# MainBoard_MCUBreakout.net
KiCad netlist of a schematic drawn in Altium Designer
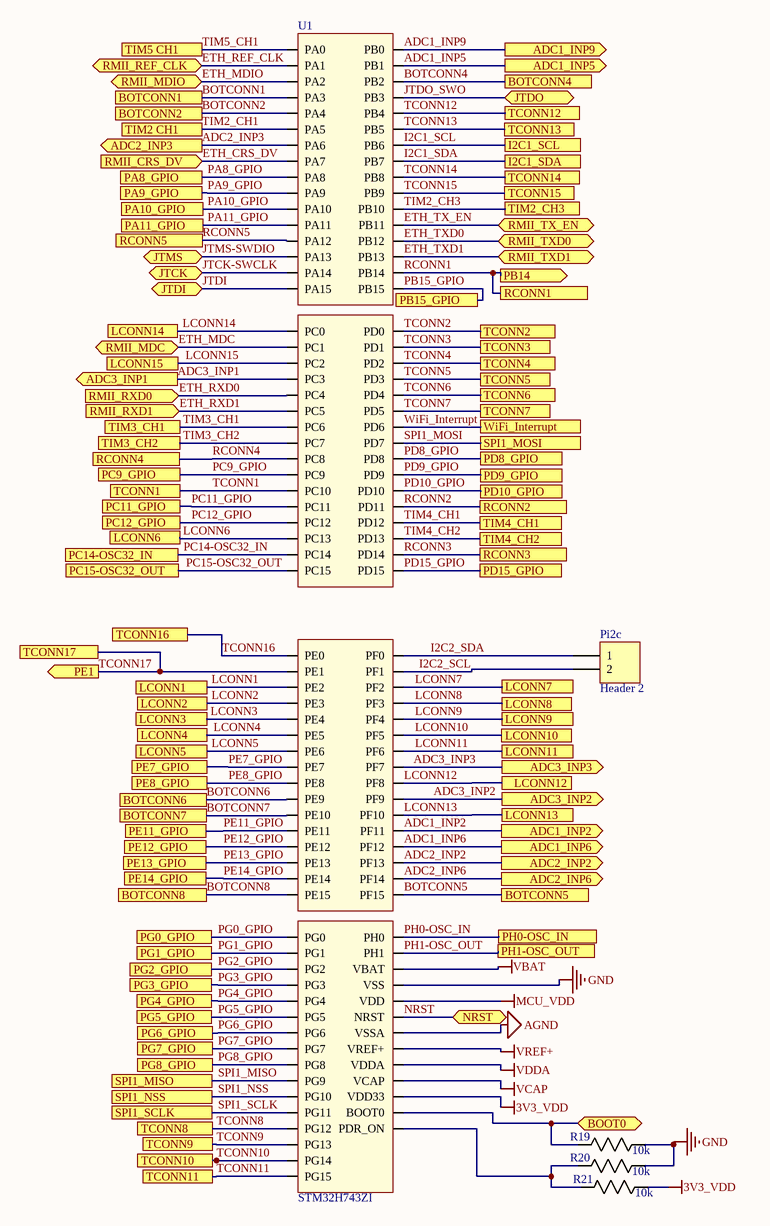
[diagram p0: MainBoard_MCUBreakout.SchDoc]

(export (version "E")
  (design (tool "Eeschema 10.0.6"))
  (components
    (comp (ref "Pi2c")
      (value "Header 2")
      (footprint "HDR1X2")
      (description "Header, 2-Pin")
      (fields (field (name "PUBLISHER") "Altium Limited"))
      (libsource (lib "Miscellaneous Connectors") (part "Header 2"))
    )
    (comp (ref "R19")
      (value "10k")
      (footprint "0805")
      (description "RES SMD 10K OHM 1% 1/8W 0805")
      (fields (field (name "MP") "RC0805FR-0710KL") (field (name "MF") "Yageo"))
      (libsource (lib "AltiumLibraries") (part "RES 10k 0805"))
    )
    (comp (ref "R20")
      (value "10k")
      (footprint "0805")
      (description "RES SMD 10K OHM 1% 1/8W 0805")
      (fields (field (name "MP") "RC0805FR-0710KL") (field (name "MF") "Yageo"))
      (libsource (lib "AltiumLibraries") (part "RES 10k 0805"))
    )
    (comp (ref "R21")
      (value "10k")
      (footprint "0805")
      (description "RES SMD 10K OHM 1% 1/8W 0805")
      (fields (field (name "MP") "RC0805FR-0710KL") (field (name "MF") "Yageo"))
      (libsource (lib "AltiumLibraries") (part "RES 10k 0805"))
    )
    (comp (ref "U1")
      (value "STM32H743ZI")
      (footprint "STM32H7")
      (fields (field (name "MF") "STMicroelectronics") (field (name "MP") "STM32H743ZIT6"))
      (libsource (lib "AltiumLibraries") (part "STM32H743ZI"))
    )
  )
  (nets
    (net (code "1") (name "/ADC1_INP2") (class "Default")
      (node (ref "U1") (pin "PF11") (pinfunction "PF11_PF11") (pintype "passive"))
    )
    (net (code "2") (name "/ADC1_INP5") (class "Default")
      (node (ref "U1") (pin "PB1") (pinfunction "PB1_PB1") (pintype "passive"))
    )
    (net (code "3") (name "/ADC1_INP6") (class "Default")
      (node (ref "U1") (pin "PF12") (pinfunction "PF12_PF12") (pintype "passive"))
    )
    (net (code "4") (name "/ADC1_INP9") (class "Default")
      (node (ref "U1") (pin "PB0") (pinfunction "PB0_PB0") (pintype "passive"))
    )
    (net (code "5") (name "/ADC2_INP2") (class "Default")
      (node (ref "U1") (pin "PF13") (pinfunction "PF13_PF13") (pintype "passive"))
    )
    (net (code "6") (name "/ADC2_INP3") (class "Default")
      (node (ref "U1") (pin "PA6") (pinfunction "PA6_PA6") (pintype "passive"))
    )
    (net (code "7") (name "/ADC2_INP6") (class "Default")
      (node (ref "U1") (pin "PF14") (pinfunction "PF14_PF14") (pintype "passive"))
    )
    (net (code "8") (name "/ADC3_INP1") (class "Default")
      (node (ref "U1") (pin "PC3") (pinfunction "PC3_PC3") (pintype "passive"))
    )
    (net (code "9") (name "/ADC3_INP2") (class "Default")
      (node (ref "U1") (pin "PF9") (pinfunction "PF9_PF9") (pintype "passive"))
    )
    (net (code "10") (name "/ADC3_INP3") (class "Default")
      (node (ref "U1") (pin "PF7") (pinfunction "PF7_PF7") (pintype "passive"))
    )
    (net (code "11") (name "/BOOT0") (class "Default")
      (node (ref "R19") (pin "2") (pinfunction "R2_2") (pintype "passive"))
      (node (ref "U1") (pin "BOOT0") (pinfunction "BOOT0_BOOT0") (pintype "passive"))
    )
    (net (code "12") (name "/BOTCONN1") (class "Default")
      (node (ref "U1") (pin "PA3") (pinfunction "PA3_PA3") (pintype "passive"))
    )
    (net (code "13") (name "/BOTCONN2") (class "Default")
      (node (ref "U1") (pin "PA4") (pinfunction "PA4_PA4") (pintype "passive"))
    )
    (net (code "14") (name "/BOTCONN4") (class "Default")
      (node (ref "U1") (pin "PB2") (pinfunction "PB2_PB2") (pintype "passive"))
    )
    (net (code "15") (name "/BOTCONN5") (class "Default")
      (node (ref "U1") (pin "PF15") (pinfunction "PF15_PF15") (pintype "passive"))
    )
    (net (code "16") (name "/BOTCONN6") (class "Default")
      (node (ref "U1") (pin "PE9") (pinfunction "PE9_PE9") (pintype "passive"))
    )
    (net (code "17") (name "/BOTCONN7") (class "Default")
      (node (ref "U1") (pin "PE10") (pinfunction "PE10_PE10") (pintype "passive"))
    )
    (net (code "18") (name "/BOTCONN8") (class "Default")
      (node (ref "U1") (pin "PE15") (pinfunction "PE15_PE15") (pintype "passive"))
    )
    (net (code "19") (name "/ETH_CRS_DV") (class "Default")
      (node (ref "U1") (pin "PA7") (pinfunction "PA7_PA7") (pintype "passive"))
    )
    (net (code "20") (name "/ETH_MDC") (class "Default")
      (node (ref "U1") (pin "PC1") (pinfunction "PC1_PC1") (pintype "passive"))
    )
    (net (code "21") (name "/ETH_MDIO") (class "Default")
      (node (ref "U1") (pin "PA2") (pinfunction "PA2_PA2") (pintype "passive"))
    )
    (net (code "22") (name "/ETH_REF_CLK") (class "Default")
      (node (ref "U1") (pin "PA1") (pinfunction "PA1_PA1") (pintype "passive"))
    )
    (net (code "23") (name "/ETH_RXD0") (class "Default")
      (node (ref "U1") (pin "PC4") (pinfunction "PC4_PC4") (pintype "passive"))
    )
    (net (code "24") (name "/ETH_RXD1") (class "Default")
      (node (ref "U1") (pin "PC5") (pinfunction "PC5_PC5") (pintype "passive"))
    )
    (net (code "25") (name "/ETH_TXD0") (class "Default")
      (node (ref "U1") (pin "PB12") (pinfunction "PB12_PB12") (pintype "passive"))
    )
    (net (code "26") (name "/ETH_TXD1") (class "Default")
      (node (ref "U1") (pin "PB13") (pinfunction "PB13_PB13") (pintype "passive"))
    )
    (net (code "27") (name "/ETH_TX_EN") (class "Default")
      (node (ref "U1") (pin "PB11") (pinfunction "PB11_PB11") (pintype "passive"))
    )
    (net (code "28") (name "/I2C1_SCL") (class "Default")
      (node (ref "U1") (pin "PB6") (pinfunction "PB6_PB6") (pintype "passive"))
    )
    (net (code "29") (name "/I2C1_SDA") (class "Default")
      (node (ref "U1") (pin "PB7") (pinfunction "PB7_PB7") (pintype "passive"))
    )
    (net (code "30") (name "/I2C2_SCL") (class "Default")
      (node (ref "Pi2c") (pin "2") (pinfunction "2_2") (pintype "passive"))
      (node (ref "U1") (pin "PF1") (pinfunction "PF1_PF1") (pintype "passive"))
    )
    (net (code "31") (name "/I2C2_SDA") (class "Default")
      (node (ref "Pi2c") (pin "1") (pinfunction "1_1") (pintype "passive"))
      (node (ref "U1") (pin "PF0") (pinfunction "PF0_PF0") (pintype "passive"))
    )
    (net (code "32") (name "/JTCK-SWCLK") (class "Default")
      (node (ref "U1") (pin "PA14") (pinfunction "PA14_PA14") (pintype "passive"))
    )
    (net (code "33") (name "/JTDI") (class "Default")
      (node (ref "U1") (pin "PA15") (pinfunction "PA15_PA15") (pintype "passive"))
    )
    (net (code "34") (name "/JTDO_SWO") (class "Default")
      (node (ref "U1") (pin "PB3") (pinfunction "PB3_PB3") (pintype "passive"))
    )
    (net (code "35") (name "/JTMS-SWDIO") (class "Default")
      (node (ref "U1") (pin "PA13") (pinfunction "PA13_PA13") (pintype "passive"))
    )
    (net (code "36") (name "/LCONN1") (class "Default")
      (node (ref "U1") (pin "PE2") (pinfunction "PE2_PE2") (pintype "passive"))
    )
    (net (code "37") (name "/LCONN2") (class "Default")
      (node (ref "U1") (pin "PE3") (pinfunction "PE3_PE3") (pintype "passive"))
    )
    (net (code "38") (name "/LCONN3") (class "Default")
      (node (ref "U1") (pin "PE4") (pinfunction "PE4_PE4") (pintype "passive"))
    )
    (net (code "39") (name "/LCONN4") (class "Default")
      (node (ref "U1") (pin "PE5") (pinfunction "PE5_PE5") (pintype "passive"))
    )
    (net (code "40") (name "/LCONN5") (class "Default")
      (node (ref "U1") (pin "PE6") (pinfunction "PE6_PE6") (pintype "passive"))
    )
    (net (code "41") (name "/LCONN6") (class "Default")
      (node (ref "U1") (pin "PC13") (pinfunction "PC13_PC13") (pintype "passive"))
    )
    (net (code "42") (name "/LCONN7") (class "Default")
      (node (ref "U1") (pin "PF2") (pinfunction "PF2_PF2") (pintype "passive"))
    )
    (net (code "43") (name "/LCONN8") (class "Default")
      (node (ref "U1") (pin "PF3") (pinfunction "PF3_PF3") (pintype "passive"))
    )
    (net (code "44") (name "/LCONN9") (class "Default")
      (node (ref "U1") (pin "PF4") (pinfunction "PF4_PF4") (pintype "passive"))
    )
    (net (code "45") (name "/LCONN10") (class "Default")
      (node (ref "U1") (pin "PF5") (pinfunction "PF5_PF5") (pintype "passive"))
    )
    (net (code "46") (name "/LCONN11") (class "Default")
      (node (ref "U1") (pin "PF6") (pinfunction "PF6_PF6") (pintype "passive"))
    )
    (net (code "47") (name "/LCONN12") (class "Default")
      (node (ref "U1") (pin "PF8") (pinfunction "PF8_PF8") (pintype "passive"))
    )
    (net (code "48") (name "/LCONN13") (class "Default")
      (node (ref "U1") (pin "PF10") (pinfunction "PF10_PF10") (pintype "passive"))
    )
    (net (code "49") (name "/LCONN14") (class "Default")
      (node (ref "U1") (pin "PC0") (pinfunction "PC0_PC0") (pintype "passive"))
    )
    (net (code "50") (name "/LCONN15") (class "Default")
      (node (ref "U1") (pin "PC2") (pinfunction "PC2_PC2") (pintype "passive"))
    )
    (net (code "51") (name "/NRST") (class "Default")
      (node (ref "U1") (pin "NRST") (pinfunction "NRST_NRST") (pintype "passive"))
    )
    (net (code "52") (name "/PA8_GPIO") (class "Default")
      (node (ref "U1") (pin "PA8") (pinfunction "PA8_PA8") (pintype "passive"))
    )
    (net (code "53") (name "/PA9_GPIO") (class "Default")
      (node (ref "U1") (pin "PA9") (pinfunction "PA9_PA9") (pintype "passive"))
    )
    (net (code "54") (name "/PA10_GPIO") (class "Default")
      (node (ref "U1") (pin "PA10") (pinfunction "PA10_PA10") (pintype "passive"))
    )
    (net (code "55") (name "/PA11_GPIO") (class "Default")
      (node (ref "U1") (pin "PA11") (pinfunction "PA11_PA11") (pintype "passive"))
    )
    (net (code "56") (name "/PB15_GPIO") (class "Default")
      (node (ref "U1") (pin "PB15") (pinfunction "PB15_PB15") (pintype "passive"))
    )
    (net (code "57") (name "/PC9_GPIO") (class "Default")
      (node (ref "U1") (pin "PC9") (pinfunction "PC9_PC9") (pintype "passive"))
    )
    (net (code "58") (name "/PC11_GPIO") (class "Default")
      (node (ref "U1") (pin "PC11") (pinfunction "PC11_PC11") (pintype "passive"))
    )
    (net (code "59") (name "/PC12_GPIO") (class "Default")
      (node (ref "U1") (pin "PC12") (pinfunction "PC12_PC12") (pintype "passive"))
    )
    (net (code "60") (name "/PC14-OSC32_IN") (class "Default")
      (node (ref "U1") (pin "PC14") (pinfunction "PC14_PC14") (pintype "passive"))
    )
    (net (code "61") (name "/PC15-OSC32_OUT") (class "Default")
      (node (ref "U1") (pin "PC15") (pinfunction "PC15_PC15") (pintype "passive"))
    )
    (net (code "62") (name "/PD8_GPIO") (class "Default")
      (node (ref "U1") (pin "PD8") (pinfunction "PD8_PD8") (pintype "passive"))
    )
    (net (code "63") (name "/PD9_GPIO") (class "Default")
      (node (ref "U1") (pin "PD9") (pinfunction "PD9_PD9") (pintype "passive"))
    )
    (net (code "64") (name "/PD10_GPIO") (class "Default")
      (node (ref "U1") (pin "PD10") (pinfunction "PD10_PD10") (pintype "passive"))
    )
    (net (code "65") (name "/PD15_GPIO") (class "Default")
      (node (ref "U1") (pin "PD15") (pinfunction "PD15_PD15") (pintype "passive"))
    )
    (net (code "66") (name "/PE7_GPIO") (class "Default")
      (node (ref "U1") (pin "PE7") (pinfunction "PE7_PE7") (pintype "passive"))
    )
    (net (code "67") (name "/PE8_GPIO") (class "Default")
      (node (ref "U1") (pin "PE8") (pinfunction "PE8_PE8") (pintype "passive"))
    )
    (net (code "68") (name "/PE11_GPIO") (class "Default")
      (node (ref "U1") (pin "PE11") (pinfunction "PE11_PE11") (pintype "passive"))
    )
    (net (code "69") (name "/PE12_GPIO") (class "Default")
      (node (ref "U1") (pin "PE12") (pinfunction "PE12_PE12") (pintype "passive"))
    )
    (net (code "70") (name "/PE13_GPIO") (class "Default")
      (node (ref "U1") (pin "PE13") (pinfunction "PE13_PE13") (pintype "passive"))
    )
    (net (code "71") (name "/PE14_GPIO") (class "Default")
      (node (ref "U1") (pin "PE14") (pinfunction "PE14_PE14") (pintype "passive"))
    )
    (net (code "72") (name "/PG0_GPIO") (class "Default")
      (node (ref "U1") (pin "PG0") (pinfunction "PG0_PG0") (pintype "passive"))
    )
    (net (code "73") (name "/PG1_GPIO") (class "Default")
      (node (ref "U1") (pin "PG1") (pinfunction "PG1_PG1") (pintype "passive"))
    )
    (net (code "74") (name "/PG2_GPIO") (class "Default")
      (node (ref "U1") (pin "PG2") (pinfunction "PG2_PG2") (pintype "passive"))
    )
    (net (code "75") (name "/PG3_GPIO") (class "Default")
      (node (ref "U1") (pin "PG3") (pinfunction "PG3_PG3") (pintype "passive"))
    )
    (net (code "76") (name "/PG4_GPIO") (class "Default")
      (node (ref "U1") (pin "PG4") (pinfunction "PG4_PG4") (pintype "passive"))
    )
    (net (code "77") (name "/PG5_GPIO") (class "Default")
      (node (ref "U1") (pin "PG5") (pinfunction "PG5_PG5") (pintype "passive"))
    )
    (net (code "78") (name "/PG6_GPIO") (class "Default")
      (node (ref "U1") (pin "PG6") (pinfunction "PG6_PG6") (pintype "passive"))
    )
    (net (code "79") (name "/PG7_GPIO") (class "Default")
      (node (ref "U1") (pin "PG7") (pinfunction "PG7_PG7") (pintype "passive"))
    )
    (net (code "80") (name "/PG8_GPIO") (class "Default")
      (node (ref "U1") (pin "PG8") (pinfunction "PG8_PG8") (pintype "passive"))
    )
    (net (code "81") (name "/PH0-OSC_IN") (class "Default")
      (node (ref "U1") (pin "PH0") (pinfunction "PH0_PH0") (pintype "passive"))
    )
    (net (code "82") (name "/PH1-OSC_OUT") (class "Default")
      (node (ref "U1") (pin "PH1") (pinfunction "PH1_PH1") (pintype "passive"))
    )
    (net (code "83") (name "/RCONN1") (class "Default")
      (node (ref "U1") (pin "PB14") (pinfunction "PB14_PB14") (pintype "passive"))
    )
    (net (code "84") (name "/RCONN2") (class "Default")
      (node (ref "U1") (pin "PD11") (pinfunction "PD11_PD11") (pintype "passive"))
    )
    (net (code "85") (name "/RCONN3") (class "Default")
      (node (ref "U1") (pin "PD14") (pinfunction "PD14_PD14") (pintype "passive"))
    )
    (net (code "86") (name "/RCONN4") (class "Default")
      (node (ref "U1") (pin "PC8") (pinfunction "PC8_PC8") (pintype "passive"))
    )
    (net (code "87") (name "/RCONN5") (class "Default")
      (node (ref "U1") (pin "PA12") (pinfunction "PA12_PA12") (pintype "passive"))
    )
    (net (code "88") (name "/SPI1_MISO") (class "Default")
      (node (ref "U1") (pin "PG9") (pinfunction "PG9_PG9") (pintype "passive"))
    )
    (net (code "89") (name "/SPI1_MOSI") (class "Default")
      (node (ref "U1") (pin "PD7") (pinfunction "PD7_PD7") (pintype "passive"))
    )
    (net (code "90") (name "/SPI1_NSS") (class "Default")
      (node (ref "U1") (pin "PG10") (pinfunction "PG10_PG10") (pintype "passive"))
    )
    (net (code "91") (name "/SPI1_SCLK") (class "Default")
      (node (ref "U1") (pin "PG11") (pinfunction "PG11_PG11") (pintype "passive"))
    )
    (net (code "92") (name "/TCONN1") (class "Default")
      (node (ref "U1") (pin "PC10") (pinfunction "PC10_PC10") (pintype "passive"))
    )
    (net (code "93") (name "/TCONN2") (class "Default")
      (node (ref "U1") (pin "PD0") (pinfunction "PD0_PD0") (pintype "passive"))
    )
    (net (code "94") (name "/TCONN3") (class "Default")
      (node (ref "U1") (pin "PD1") (pinfunction "PD1_PD1") (pintype "passive"))
    )
    (net (code "95") (name "/TCONN4") (class "Default")
      (node (ref "U1") (pin "PD2") (pinfunction "PD2_PD2") (pintype "passive"))
    )
    (net (code "96") (name "/TCONN5") (class "Default")
      (node (ref "U1") (pin "PD3") (pinfunction "PD3_PD3") (pintype "passive"))
    )
    (net (code "97") (name "/TCONN6") (class "Default")
      (node (ref "U1") (pin "PD4") (pinfunction "PD4_PD4") (pintype "passive"))
    )
    (net (code "98") (name "/TCONN7") (class "Default")
      (node (ref "U1") (pin "PD5") (pinfunction "PD5_PD5") (pintype "passive"))
    )
    (net (code "99") (name "/TCONN8") (class "Default")
      (node (ref "U1") (pin "PG12") (pinfunction "PG12_PG12") (pintype "passive"))
    )
    (net (code "100") (name "/TCONN9") (class "Default")
      (node (ref "U1") (pin "PG13") (pinfunction "PG13_PG13") (pintype "passive"))
    )
    (net (code "101") (name "/TCONN10") (class "Default")
      (node (ref "U1") (pin "PG14") (pinfunction "PG14_PG14") (pintype "passive"))
    )
    (net (code "102") (name "/TCONN11") (class "Default")
      (node (ref "U1") (pin "PG15") (pinfunction "PG15_PG15") (pintype "passive"))
    )
    (net (code "103") (name "/TCONN12") (class "Default")
      (node (ref "U1") (pin "PB4") (pinfunction "PB4_PB4") (pintype "passive"))
    )
    (net (code "104") (name "/TCONN13") (class "Default")
      (node (ref "U1") (pin "PB5") (pinfunction "PB5_PB5") (pintype "passive"))
    )
    (net (code "105") (name "/TCONN14") (class "Default")
      (node (ref "U1") (pin "PB8") (pinfunction "PB8_PB8") (pintype "passive"))
    )
    (net (code "106") (name "/TCONN15") (class "Default")
      (node (ref "U1") (pin "PB9") (pinfunction "PB9_PB9") (pintype "passive"))
    )
    (net (code "107") (name "/TCONN16") (class "Default")
      (node (ref "U1") (pin "PE0") (pinfunction "PE0_PE0") (pintype "passive"))
    )
    (net (code "108") (name "/TCONN17") (class "Default")
      (node (ref "U1") (pin "PE1") (pinfunction "PE1_PE1") (pintype "passive"))
    )
    (net (code "109") (name "/TIM2_CH1") (class "Default")
      (node (ref "U1") (pin "PA5") (pinfunction "PA5_PA5") (pintype "passive"))
    )
    (net (code "110") (name "/TIM2_CH3") (class "Default")
      (node (ref "U1") (pin "PB10") (pinfunction "PB10_PB10") (pintype "passive"))
    )
    (net (code "111") (name "/TIM3_CH1") (class "Default")
      (node (ref "U1") (pin "PC6") (pinfunction "PC6_PC6") (pintype "passive"))
    )
    (net (code "112") (name "/TIM3_CH2") (class "Default")
      (node (ref "U1") (pin "PC7") (pinfunction "PC7_PC7") (pintype "passive"))
    )
    (net (code "113") (name "/TIM4_CH1") (class "Default")
      (node (ref "U1") (pin "PD12") (pinfunction "PD12_PD12") (pintype "passive"))
    )
    (net (code "114") (name "/TIM4_CH2") (class "Default")
      (node (ref "U1") (pin "PD13") (pinfunction "PD13_PD13") (pintype "passive"))
    )
    (net (code "115") (name "/TIM5_CH1") (class "Default")
      (node (ref "U1") (pin "PA0") (pinfunction "PA0_PA0") (pintype "passive"))
    )
    (net (code "116") (name "/WiFi_Interrupt") (class "Default")
      (node (ref "U1") (pin "PD6") (pinfunction "PD6_PD6") (pintype "passive"))
    )
    (net (code "117") (name "3V3_VDD") (class "Default")
      (node (ref "R21") (pin "1") (pinfunction "R1_1") (pintype "passive"))
      (node (ref "U1") (pin "VDD33USB") (pinfunction "VDD33_VDD33USB") (pintype "passive"))
    )
    (net (code "118") (name "AGND") (class "Default")
      (node (ref "U1") (pin "VSSA") (pinfunction "VSSA_VSSA") (pintype "passive"))
    )
    (net (code "119") (name "GND") (class "Default")
      (node (ref "R19") (pin "1") (pinfunction "R1_1") (pintype "passive"))
      (node (ref "R20") (pin "1") (pinfunction "R1_1") (pintype "passive"))
      (node (ref "U1") (pin "VSS") (pinfunction "VSS_VSS") (pintype "passive"))
    )
    (net (code "120") (name "MCU_VDD") (class "Default")
      (node (ref "U1") (pin "VDD") (pinfunction "VDD_VDD") (pintype "passive"))
    )
    (net (code "121") (name "Net-(R20-R2)") (class "Default")
      (node (ref "R20") (pin "2") (pinfunction "R2_2") (pintype "passive"))
      (node (ref "R21") (pin "2") (pinfunction "R2_2") (pintype "passive"))
      (node (ref "U1") (pin "PDR_ON") (pinfunction "PDR_ON_PDR_ON") (pintype "passive"))
    )
    (net (code "122") (name "VBAT") (class "Default")
      (node (ref "U1") (pin "VBAT") (pinfunction "VBAT_VBAT") (pintype "passive"))
    )
    (net (code "123") (name "VCAP") (class "Default")
      (node (ref "U1") (pin "VCAP") (pinfunction "VCAP_VCAP") (pintype "passive"))
    )
    (net (code "124") (name "VDDA") (class "Default")
      (node (ref "U1") (pin "VDDA") (pinfunction "VDDA_VDDA") (pintype "passive"))
    )
    (net (code "125") (name "VREF+") (class "Default")
      (node (ref "U1") (pin "VREF+") (pinfunction "VREF+_VREF+") (pintype "passive"))
    )
  )
)
